# CombCombiner.net
KiCad netlist of a schematic drawn in Altium Designer
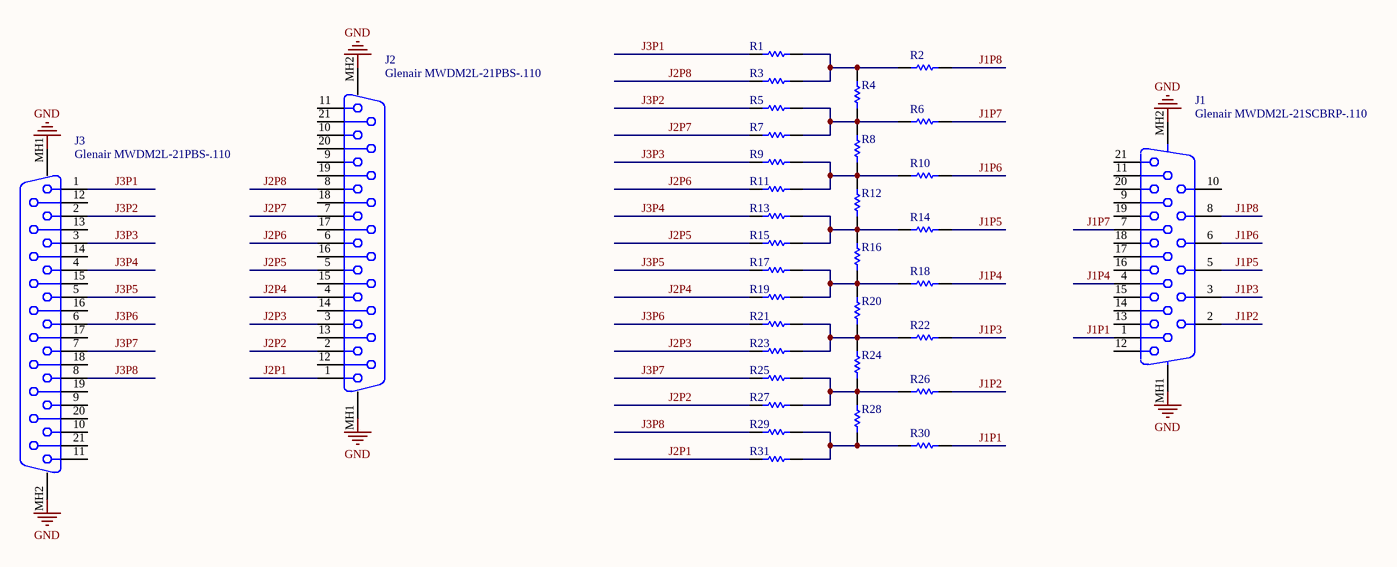
[diagram p0: CombCombiner.SchDoc]

(export (version "E")
  (design (tool "Eeschema 10.0.6"))
  (components
    (comp (ref "J1")
      (value "Glenair MWDM2L-21SCBRP-.110")
      (footprint "MicroD21Glenair-RA3row")
      (description "GlenairMicroDsub21 - 3 row")
      (libsource (lib "CombCombiner") (part "GlenairMicroDsub21-3row"))
    )
    (comp (ref "J2")
      (value "Glenair MWDM2L-21PBS-.110")
      (footprint "MicroD21Glenair-Vert2row")
      (description "GlenairMicroDsub21 -2 row")
      (libsource (lib "CombCombiner") (part "GlenairMicroDsub21 -2 row"))
    )
    (comp (ref "J3")
      (value "Glenair MWDM2L-21PBS-.110")
      (footprint "MicroD21Glenair-Vert2row")
      (description "GlenairMicroDsub21 -2 row")
      (libsource (lib "CombCombiner") (part "GlenairMicroDsub21 -2 row"))
    )
    (comp (ref "R1")
      (value "Res0603")
      (footprint "0603")
      (description "RES 100K OHM 1/10W 1% 0603 SMD")
      (fields (field (name "MANUFACTURER") "e.g Vishay/Dale"))
      (libsource (lib "CombCombiner") (part "Res0603"))
    )
    (comp (ref "R2")
      (value "Res0603")
      (footprint "0603")
      (description "RES 100K OHM 1/10W 1% 0603 SMD")
      (fields (field (name "MANUFACTURER") "e.g Vishay/Dale"))
      (libsource (lib "CombCombiner") (part "Res0603"))
    )
    (comp (ref "R3")
      (value "Res0603")
      (footprint "0603")
      (description "RES 100K OHM 1/10W 1% 0603 SMD")
      (fields (field (name "MANUFACTURER") "e.g Vishay/Dale"))
      (libsource (lib "CombCombiner") (part "Res0603"))
    )
    (comp (ref "R4")
      (value "Res0603")
      (footprint "0603")
      (description "RES 100K OHM 1/10W 1% 0603 SMD")
      (fields (field (name "MANUFACTURER") "e.g Vishay/Dale"))
      (libsource (lib "CombCombiner") (part "Res0603"))
    )
    (comp (ref "R5")
      (value "Res0603")
      (footprint "0603")
      (description "RES 100K OHM 1/10W 1% 0603 SMD")
      (fields (field (name "MANUFACTURER") "e.g Vishay/Dale"))
      (libsource (lib "CombCombiner") (part "Res0603"))
    )
    (comp (ref "R6")
      (value "Res0603")
      (footprint "0603")
      (description "RES 100K OHM 1/10W 1% 0603 SMD")
      (fields (field (name "MANUFACTURER") "e.g Vishay/Dale"))
      (libsource (lib "CombCombiner") (part "Res0603"))
    )
    (comp (ref "R7")
      (value "Res0603")
      (footprint "0603")
      (description "RES 100K OHM 1/10W 1% 0603 SMD")
      (fields (field (name "MANUFACTURER") "e.g Vishay/Dale"))
      (libsource (lib "CombCombiner") (part "Res0603"))
    )
    (comp (ref "R8")
      (value "Res0603")
      (footprint "0603")
      (description "RES 100K OHM 1/10W 1% 0603 SMD")
      (fields (field (name "MANUFACTURER") "e.g Vishay/Dale"))
      (libsource (lib "CombCombiner") (part "Res0603"))
    )
    (comp (ref "R9")
      (value "Res0603")
      (footprint "0603")
      (description "RES 100K OHM 1/10W 1% 0603 SMD")
      (fields (field (name "MANUFACTURER") "e.g Vishay/Dale"))
      (libsource (lib "CombCombiner") (part "Res0603"))
    )
    (comp (ref "R10")
      (value "Res0603")
      (footprint "0603")
      (description "RES 100K OHM 1/10W 1% 0603 SMD")
      (fields (field (name "MANUFACTURER") "e.g Vishay/Dale"))
      (libsource (lib "CombCombiner") (part "Res0603"))
    )
    (comp (ref "R11")
      (value "Res0603")
      (footprint "0603")
      (description "RES 100K OHM 1/10W 1% 0603 SMD")
      (fields (field (name "MANUFACTURER") "e.g Vishay/Dale"))
      (libsource (lib "CombCombiner") (part "Res0603"))
    )
    (comp (ref "R12")
      (value "Res0603")
      (footprint "0603")
      (description "RES 100K OHM 1/10W 1% 0603 SMD")
      (fields (field (name "MANUFACTURER") "e.g Vishay/Dale"))
      (libsource (lib "CombCombiner") (part "Res0603"))
    )
    (comp (ref "R13")
      (value "Res0603")
      (footprint "0603")
      (description "RES 100K OHM 1/10W 1% 0603 SMD")
      (fields (field (name "MANUFACTURER") "e.g Vishay/Dale"))
      (libsource (lib "CombCombiner") (part "Res0603"))
    )
    (comp (ref "R14")
      (value "Res0603")
      (footprint "0603")
      (description "RES 100K OHM 1/10W 1% 0603 SMD")
      (fields (field (name "MANUFACTURER") "e.g Vishay/Dale"))
      (libsource (lib "CombCombiner") (part "Res0603"))
    )
    (comp (ref "R15")
      (value "Res0603")
      (footprint "0603")
      (description "RES 100K OHM 1/10W 1% 0603 SMD")
      (fields (field (name "MANUFACTURER") "e.g Vishay/Dale"))
      (libsource (lib "CombCombiner") (part "Res0603"))
    )
    (comp (ref "R16")
      (value "Res0603")
      (footprint "0603")
      (description "RES 100K OHM 1/10W 1% 0603 SMD")
      (fields (field (name "MANUFACTURER") "e.g Vishay/Dale"))
      (libsource (lib "CombCombiner") (part "Res0603"))
    )
    (comp (ref "R17")
      (value "Res0603")
      (footprint "0603")
      (description "RES 100K OHM 1/10W 1% 0603 SMD")
      (fields (field (name "MANUFACTURER") "e.g Vishay/Dale"))
      (libsource (lib "CombCombiner") (part "Res0603"))
    )
    (comp (ref "R18")
      (value "Res0603")
      (footprint "0603")
      (description "RES 100K OHM 1/10W 1% 0603 SMD")
      (fields (field (name "MANUFACTURER") "e.g Vishay/Dale"))
      (libsource (lib "CombCombiner") (part "Res0603"))
    )
    (comp (ref "R19")
      (value "Res0603")
      (footprint "0603")
      (description "RES 100K OHM 1/10W 1% 0603 SMD")
      (fields (field (name "MANUFACTURER") "e.g Vishay/Dale"))
      (libsource (lib "CombCombiner") (part "Res0603"))
    )
    (comp (ref "R20")
      (value "Res0603")
      (footprint "0603")
      (description "RES 100K OHM 1/10W 1% 0603 SMD")
      (fields (field (name "MANUFACTURER") "e.g Vishay/Dale"))
      (libsource (lib "CombCombiner") (part "Res0603"))
    )
    (comp (ref "R21")
      (value "Res0603")
      (footprint "0603")
      (description "RES 100K OHM 1/10W 1% 0603 SMD")
      (fields (field (name "MANUFACTURER") "e.g Vishay/Dale"))
      (libsource (lib "CombCombiner") (part "Res0603"))
    )
    (comp (ref "R22")
      (value "Res0603")
      (footprint "0603")
      (description "RES 100K OHM 1/10W 1% 0603 SMD")
      (fields (field (name "MANUFACTURER") "e.g Vishay/Dale"))
      (libsource (lib "CombCombiner") (part "Res0603"))
    )
    (comp (ref "R23")
      (value "Res0603")
      (footprint "0603")
      (description "RES 100K OHM 1/10W 1% 0603 SMD")
      (fields (field (name "MANUFACTURER") "e.g Vishay/Dale"))
      (libsource (lib "CombCombiner") (part "Res0603"))
    )
    (comp (ref "R24")
      (value "Res0603")
      (footprint "0603")
      (description "RES 100K OHM 1/10W 1% 0603 SMD")
      (fields (field (name "MANUFACTURER") "e.g Vishay/Dale"))
      (libsource (lib "CombCombiner") (part "Res0603"))
    )
    (comp (ref "R25")
      (value "Res0603")
      (footprint "0603")
      (description "RES 100K OHM 1/10W 1% 0603 SMD")
      (fields (field (name "MANUFACTURER") "e.g Vishay/Dale"))
      (libsource (lib "CombCombiner") (part "Res0603"))
    )
    (comp (ref "R26")
      (value "Res0603")
      (footprint "0603")
      (description "RES 100K OHM 1/10W 1% 0603 SMD")
      (fields (field (name "MANUFACTURER") "e.g Vishay/Dale"))
      (libsource (lib "CombCombiner") (part "Res0603"))
    )
    (comp (ref "R27")
      (value "Res0603")
      (footprint "0603")
      (description "RES 100K OHM 1/10W 1% 0603 SMD")
      (fields (field (name "MANUFACTURER") "e.g Vishay/Dale"))
      (libsource (lib "CombCombiner") (part "Res0603"))
    )
    (comp (ref "R28")
      (value "Res0603")
      (footprint "0603")
      (description "RES 100K OHM 1/10W 1% 0603 SMD")
      (fields (field (name "MANUFACTURER") "e.g Vishay/Dale"))
      (libsource (lib "CombCombiner") (part "Res0603"))
    )
    (comp (ref "R29")
      (value "Res0603")
      (footprint "0603")
      (description "RES 100K OHM 1/10W 1% 0603 SMD")
      (fields (field (name "MANUFACTURER") "e.g Vishay/Dale"))
      (libsource (lib "CombCombiner") (part "Res0603"))
    )
    (comp (ref "R30")
      (value "Res0603")
      (footprint "0603")
      (description "RES 100K OHM 1/10W 1% 0603 SMD")
      (fields (field (name "MANUFACTURER") "e.g Vishay/Dale"))
      (libsource (lib "CombCombiner") (part "Res0603"))
    )
    (comp (ref "R31")
      (value "Res0603")
      (footprint "0603")
      (description "RES 100K OHM 1/10W 1% 0603 SMD")
      (fields (field (name "MANUFACTURER") "e.g Vishay/Dale"))
      (libsource (lib "CombCombiner") (part "Res0603"))
    )
  )
  (nets
    (net (code "1") (name "/J1P1") (class "Default")
      (node (ref "J1") (pin "1") (pinfunction "1_1") (pintype "passive"))
      (node (ref "R30") (pin "1") (pinfunction "1_1") (pintype "passive"))
    )
    (net (code "2") (name "/J1P2") (class "Default")
      (node (ref "J1") (pin "2") (pinfunction "2_2") (pintype "passive"))
      (node (ref "R26") (pin "1") (pinfunction "1_1") (pintype "passive"))
    )
    (net (code "3") (name "/J1P3") (class "Default")
      (node (ref "J1") (pin "3") (pinfunction "3_3") (pintype "passive"))
      (node (ref "R22") (pin "1") (pinfunction "1_1") (pintype "passive"))
    )
    (net (code "4") (name "/J1P4") (class "Default")
      (node (ref "J1") (pin "4") (pinfunction "4_4") (pintype "passive"))
      (node (ref "R18") (pin "1") (pinfunction "1_1") (pintype "passive"))
    )
    (net (code "5") (name "/J1P5") (class "Default")
      (node (ref "J1") (pin "5") (pinfunction "5_5") (pintype "passive"))
      (node (ref "R14") (pin "1") (pinfunction "1_1") (pintype "passive"))
    )
    (net (code "6") (name "/J1P6") (class "Default")
      (node (ref "J1") (pin "6") (pinfunction "6_6") (pintype "passive"))
      (node (ref "R10") (pin "1") (pinfunction "1_1") (pintype "passive"))
    )
    (net (code "7") (name "/J1P7") (class "Default")
      (node (ref "J1") (pin "7") (pinfunction "7_7") (pintype "passive"))
      (node (ref "R6") (pin "1") (pinfunction "1_1") (pintype "passive"))
    )
    (net (code "8") (name "/J1P8") (class "Default")
      (node (ref "J1") (pin "8") (pinfunction "8_8") (pintype "passive"))
      (node (ref "R2") (pin "2") (pinfunction "2_2") (pintype "passive"))
    )
    (net (code "9") (name "/J2P1") (class "Default")
      (node (ref "J2") (pin "1") (pinfunction "1_1") (pintype "passive"))
      (node (ref "R31") (pin "2") (pinfunction "2_2") (pintype "passive"))
    )
    (net (code "10") (name "/J2P2") (class "Default")
      (node (ref "J2") (pin "2") (pinfunction "2_2") (pintype "passive"))
      (node (ref "R27") (pin "2") (pinfunction "2_2") (pintype "passive"))
    )
    (net (code "11") (name "/J2P3") (class "Default")
      (node (ref "J2") (pin "3") (pinfunction "3_3") (pintype "passive"))
      (node (ref "R23") (pin "2") (pinfunction "2_2") (pintype "passive"))
    )
    (net (code "12") (name "/J2P4") (class "Default")
      (node (ref "J2") (pin "4") (pinfunction "4_4") (pintype "passive"))
      (node (ref "R19") (pin "2") (pinfunction "2_2") (pintype "passive"))
    )
    (net (code "13") (name "/J2P5") (class "Default")
      (node (ref "J2") (pin "5") (pinfunction "5_5") (pintype "passive"))
      (node (ref "R15") (pin "2") (pinfunction "2_2") (pintype "passive"))
    )
    (net (code "14") (name "/J2P6") (class "Default")
      (node (ref "J2") (pin "6") (pinfunction "6_6") (pintype "passive"))
      (node (ref "R11") (pin "2") (pinfunction "2_2") (pintype "passive"))
    )
    (net (code "15") (name "/J2P7") (class "Default")
      (node (ref "J2") (pin "7") (pinfunction "7_7") (pintype "passive"))
      (node (ref "R7") (pin "2") (pinfunction "2_2") (pintype "passive"))
    )
    (net (code "16") (name "/J2P8") (class "Default")
      (node (ref "J2") (pin "8") (pinfunction "8_8") (pintype "passive"))
      (node (ref "R3") (pin "2") (pinfunction "2_2") (pintype "passive"))
    )
    (net (code "17") (name "/J3P1") (class "Default")
      (node (ref "J3") (pin "1") (pinfunction "1_1") (pintype "passive"))
      (node (ref "R1") (pin "2") (pinfunction "2_2") (pintype "passive"))
    )
    (net (code "18") (name "/J3P2") (class "Default")
      (node (ref "J3") (pin "2") (pinfunction "2_2") (pintype "passive"))
      (node (ref "R5") (pin "2") (pinfunction "2_2") (pintype "passive"))
    )
    (net (code "19") (name "/J3P3") (class "Default")
      (node (ref "J3") (pin "3") (pinfunction "3_3") (pintype "passive"))
      (node (ref "R9") (pin "2") (pinfunction "2_2") (pintype "passive"))
    )
    (net (code "20") (name "/J3P4") (class "Default")
      (node (ref "J3") (pin "4") (pinfunction "4_4") (pintype "passive"))
      (node (ref "R13") (pin "2") (pinfunction "2_2") (pintype "passive"))
    )
    (net (code "21") (name "/J3P5") (class "Default")
      (node (ref "J3") (pin "5") (pinfunction "5_5") (pintype "passive"))
      (node (ref "R17") (pin "2") (pinfunction "2_2") (pintype "passive"))
    )
    (net (code "22") (name "/J3P6") (class "Default")
      (node (ref "J3") (pin "6") (pinfunction "6_6") (pintype "passive"))
      (node (ref "R21") (pin "2") (pinfunction "2_2") (pintype "passive"))
    )
    (net (code "23") (name "/J3P7") (class "Default")
      (node (ref "J3") (pin "7") (pinfunction "7_7") (pintype "passive"))
      (node (ref "R25") (pin "2") (pinfunction "2_2") (pintype "passive"))
    )
    (net (code "24") (name "/J3P8") (class "Default")
      (node (ref "J3") (pin "8") (pinfunction "8_8") (pintype "passive"))
      (node (ref "R29") (pin "2") (pinfunction "2_2") (pintype "passive"))
    )
    (net (code "25") (name "GND") (class "Default")
      (node (ref "J1") (pin "MH1") (pinfunction "MH1_MH1") (pintype "passive"))
      (node (ref "J1") (pin "MH2") (pinfunction "MH2_MH2") (pintype "passive"))
      (node (ref "J2") (pin "MH1") (pinfunction "MH1_MH1") (pintype "passive"))
      (node (ref "J2") (pin "MH2") (pinfunction "MH2_MH2") (pintype "passive"))
      (node (ref "J3") (pin "MH1") (pinfunction "MH1_MH1") (pintype "passive"))
      (node (ref "J3") (pin "MH2") (pinfunction "MH2_MH2") (pintype "passive"))
    )
    (net (code "26") (name "Net-(R1-Pad1)") (class "Default")
      (node (ref "R1") (pin "1") (pinfunction "1_1") (pintype "passive"))
      (node (ref "R2") (pin "1") (pinfunction "1_1") (pintype "passive"))
      (node (ref "R3") (pin "1") (pinfunction "1_1") (pintype "passive"))
      (node (ref "R4") (pin "2") (pinfunction "2_2") (pintype "passive"))
    )
    (net (code "27") (name "Net-(R4-Pad1)") (class "Default")
      (node (ref "R4") (pin "1") (pinfunction "1_1") (pintype "passive"))
      (node (ref "R5") (pin "1") (pinfunction "1_1") (pintype "passive"))
      (node (ref "R6") (pin "2") (pinfunction "2_2") (pintype "passive"))
      (node (ref "R7") (pin "1") (pinfunction "1_1") (pintype "passive"))
      (node (ref "R8") (pin "2") (pinfunction "2_2") (pintype "passive"))
    )
    (net (code "28") (name "Net-(R10-Pad2)") (class "Default")
      (node (ref "R10") (pin "2") (pinfunction "2_2") (pintype "passive"))
      (node (ref "R11") (pin "1") (pinfunction "1_1") (pintype "passive"))
      (node (ref "R12") (pin "2") (pinfunction "2_2") (pintype "passive"))
      (node (ref "R8") (pin "1") (pinfunction "1_1") (pintype "passive"))
      (node (ref "R9") (pin "1") (pinfunction "1_1") (pintype "passive"))
    )
    (net (code "29") (name "Net-(R12-Pad1)") (class "Default")
      (node (ref "R12") (pin "1") (pinfunction "1_1") (pintype "passive"))
      (node (ref "R13") (pin "1") (pinfunction "1_1") (pintype "passive"))
      (node (ref "R14") (pin "2") (pinfunction "2_2") (pintype "passive"))
      (node (ref "R15") (pin "1") (pinfunction "1_1") (pintype "passive"))
      (node (ref "R16") (pin "2") (pinfunction "2_2") (pintype "passive"))
    )
    (net (code "30") (name "Net-(R16-Pad1)") (class "Default")
      (node (ref "R16") (pin "1") (pinfunction "1_1") (pintype "passive"))
      (node (ref "R17") (pin "1") (pinfunction "1_1") (pintype "passive"))
      (node (ref "R18") (pin "2") (pinfunction "2_2") (pintype "passive"))
      (node (ref "R19") (pin "1") (pinfunction "1_1") (pintype "passive"))
      (node (ref "R20") (pin "2") (pinfunction "2_2") (pintype "passive"))
    )
    (net (code "31") (name "Net-(R20-Pad1)") (class "Default")
      (node (ref "R20") (pin "1") (pinfunction "1_1") (pintype "passive"))
      (node (ref "R21") (pin "1") (pinfunction "1_1") (pintype "passive"))
      (node (ref "R22") (pin "2") (pinfunction "2_2") (pintype "passive"))
      (node (ref "R23") (pin "1") (pinfunction "1_1") (pintype "passive"))
      (node (ref "R24") (pin "2") (pinfunction "2_2") (pintype "passive"))
    )
    (net (code "32") (name "Net-(R24-Pad1)") (class "Default")
      (node (ref "R24") (pin "1") (pinfunction "1_1") (pintype "passive"))
      (node (ref "R25") (pin "1") (pinfunction "1_1") (pintype "passive"))
      (node (ref "R26") (pin "2") (pinfunction "2_2") (pintype "passive"))
      (node (ref "R27") (pin "1") (pinfunction "1_1") (pintype "passive"))
      (node (ref "R28") (pin "2") (pinfunction "2_2") (pintype "passive"))
    )
    (net (code "33") (name "Net-(R28-Pad1)") (class "Default")
      (node (ref "R28") (pin "1") (pinfunction "1_1") (pintype "passive"))
      (node (ref "R29") (pin "1") (pinfunction "1_1") (pintype "passive"))
      (node (ref "R30") (pin "2") (pinfunction "2_2") (pintype "passive"))
      (node (ref "R31") (pin "1") (pinfunction "1_1") (pintype "passive"))
    )
    (net (code "34") (name "unconnected-(J1-Pad9)") (class "Default")
      (node (ref "J1") (pin "9") (pinfunction "9_9") (pintype "passive"))
    )
    (net (code "35") (name "unconnected-(J1-Pad10)") (class "Default")
      (node (ref "J1") (pin "10") (pinfunction "10_10") (pintype "passive"))
    )
    (net (code "36") (name "unconnected-(J1-Pad11)") (class "Default")
      (node (ref "J1") (pin "11") (pinfunction "11_11") (pintype "passive"))
    )
    (net (code "37") (name "unconnected-(J1-Pad12)") (class "Default")
      (node (ref "J1") (pin "12") (pinfunction "12_12") (pintype "passive"))
    )
    (net (code "38") (name "unconnected-(J1-Pad13)") (class "Default")
      (node (ref "J1") (pin "13") (pinfunction "13_13") (pintype "passive"))
    )
    (net (code "39") (name "unconnected-(J1-Pad14)") (class "Default")
      (node (ref "J1") (pin "14") (pinfunction "14_14") (pintype "passive"))
    )
    (net (code "40") (name "unconnected-(J1-Pad15)") (class "Default")
      (node (ref "J1") (pin "15") (pinfunction "15_15") (pintype "passive"))
    )
    (net (code "41") (name "unconnected-(J1-Pad16)") (class "Default")
      (node (ref "J1") (pin "16") (pinfunction "16_16") (pintype "passive"))
    )
    (net (code "42") (name "unconnected-(J1-Pad17)") (class "Default")
      (node (ref "J1") (pin "17") (pinfunction "17_17") (pintype "passive"))
    )
    (net (code "43") (name "unconnected-(J1-Pad18)") (class "Default")
      (node (ref "J1") (pin "18") (pinfunction "18_18") (pintype "passive"))
    )
    (net (code "44") (name "unconnected-(J1-Pad19)") (class "Default")
      (node (ref "J1") (pin "19") (pinfunction "19_19") (pintype "passive"))
    )
    (net (code "45") (name "unconnected-(J1-Pad20)") (class "Default")
      (node (ref "J1") (pin "20") (pinfunction "20_20") (pintype "passive"))
    )
    (net (code "46") (name "unconnected-(J1-Pad21)") (class "Default")
      (node (ref "J1") (pin "21") (pinfunction "21_21") (pintype "passive"))
    )
    (net (code "47") (name "unconnected-(J2-Pad9)") (class "Default")
      (node (ref "J2") (pin "9") (pinfunction "9_9") (pintype "passive"))
    )
    (net (code "48") (name "unconnected-(J2-Pad10)") (class "Default")
      (node (ref "J2") (pin "10") (pinfunction "10_10") (pintype "passive"))
    )
    (net (code "49") (name "unconnected-(J2-Pad11)") (class "Default")
      (node (ref "J2") (pin "11") (pinfunction "11_11") (pintype "passive"))
    )
    (net (code "50") (name "unconnected-(J2-Pad12)") (class "Default")
      (node (ref "J2") (pin "12") (pinfunction "12_12") (pintype "passive"))
    )
    (net (code "51") (name "unconnected-(J2-Pad13)") (class "Default")
      (node (ref "J2") (pin "13") (pinfunction "13_13") (pintype "passive"))
    )
    (net (code "52") (name "unconnected-(J2-Pad14)") (class "Default")
      (node (ref "J2") (pin "14") (pinfunction "14_14") (pintype "passive"))
    )
    (net (code "53") (name "unconnected-(J2-Pad15)") (class "Default")
      (node (ref "J2") (pin "15") (pinfunction "15_15") (pintype "passive"))
    )
    (net (code "54") (name "unconnected-(J2-Pad16)") (class "Default")
      (node (ref "J2") (pin "16") (pinfunction "16_16") (pintype "passive"))
    )
    (net (code "55") (name "unconnected-(J2-Pad17)") (class "Default")
      (node (ref "J2") (pin "17") (pinfunction "17_17") (pintype "passive"))
    )
    (net (code "56") (name "unconnected-(J2-Pad18)") (class "Default")
      (node (ref "J2") (pin "18") (pinfunction "18_18") (pintype "passive"))
    )
    (net (code "57") (name "unconnected-(J2-Pad19)") (class "Default")
      (node (ref "J2") (pin "19") (pinfunction "19_19") (pintype "passive"))
    )
    (net (code "58") (name "unconnected-(J2-Pad20)") (class "Default")
      (node (ref "J2") (pin "20") (pinfunction "20_20") (pintype "passive"))
    )
    (net (code "59") (name "unconnected-(J2-Pad21)") (class "Default")
      (node (ref "J2") (pin "21") (pinfunction "21_21") (pintype "passive"))
    )
    (net (code "60") (name "unconnected-(J3-Pad9)") (class "Default")
      (node (ref "J3") (pin "9") (pinfunction "9_9") (pintype "passive"))
    )
    (net (code "61") (name "unconnected-(J3-Pad10)") (class "Default")
      (node (ref "J3") (pin "10") (pinfunction "10_10") (pintype "passive"))
    )
    (net (code "62") (name "unconnected-(J3-Pad11)") (class "Default")
      (node (ref "J3") (pin "11") (pinfunction "11_11") (pintype "passive"))
    )
    (net (code "63") (name "unconnected-(J3-Pad12)") (class "Default")
      (node (ref "J3") (pin "12") (pinfunction "12_12") (pintype "passive"))
    )
    (net (code "64") (name "unconnected-(J3-Pad13)") (class "Default")
      (node (ref "J3") (pin "13") (pinfunction "13_13") (pintype "passive"))
    )
    (net (code "65") (name "unconnected-(J3-Pad14)") (class "Default")
      (node (ref "J3") (pin "14") (pinfunction "14_14") (pintype "passive"))
    )
    (net (code "66") (name "unconnected-(J3-Pad15)") (class "Default")
      (node (ref "J3") (pin "15") (pinfunction "15_15") (pintype "passive"))
    )
    (net (code "67") (name "unconnected-(J3-Pad16)") (class "Default")
      (node (ref "J3") (pin "16") (pinfunction "16_16") (pintype "passive"))
    )
    (net (code "68") (name "unconnected-(J3-Pad17)") (class "Default")
      (node (ref "J3") (pin "17") (pinfunction "17_17") (pintype "passive"))
    )
    (net (code "69") (name "unconnected-(J3-Pad18)") (class "Default")
      (node (ref "J3") (pin "18") (pinfunction "18_18") (pintype "passive"))
    )
    (net (code "70") (name "unconnected-(J3-Pad19)") (class "Default")
      (node (ref "J3") (pin "19") (pinfunction "19_19") (pintype "passive"))
    )
    (net (code "71") (name "unconnected-(J3-Pad20)") (class "Default")
      (node (ref "J3") (pin "20") (pinfunction "20_20") (pintype "passive"))
    )
    (net (code "72") (name "unconnected-(J3-Pad21)") (class "Default")
      (node (ref "J3") (pin "21") (pinfunction "21_21") (pintype "passive"))
    )
  )
)
